# TOP.net
KiCad netlist of a schematic drawn in Altium Designer
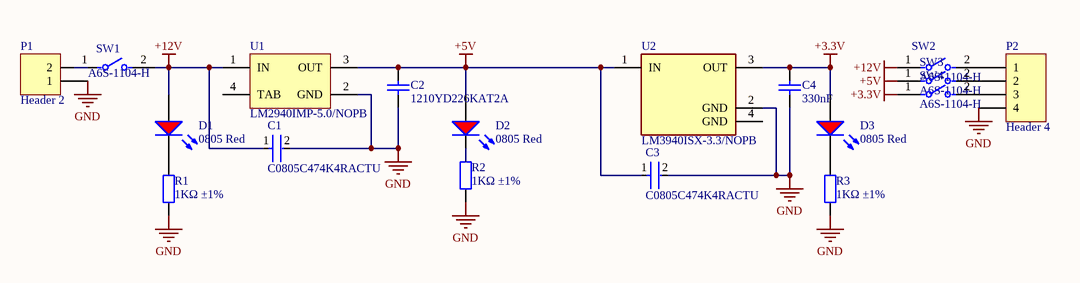
[diagram p0: TOP.SchDoc]

(export (version "E")
  (design (tool "Eeschema 10.0.6"))
  (components
    (comp (ref "C1")
      (value "C0805C474K4RACTU")
      (footprint "FP-C0805C-DN-MFG")
      (description "CAP CER 0.47UF 16V 10% X7R 0805")
      (fields
        (field (name "MANUFACTURER") "KEMET")
        (field (name "OCTOPART") "https://octopart.com/c0805c474k4ractu-kemet-107561")
      )
      (libsource (lib "Altium Content Vault") (part "b4654b650e69147ec39a6b967a45e02"))
    )
    (comp (ref "C2")
      (value "1210YD226KAT2A")
      (footprint "CAPC3225X279X50LL20T25")
      (description "Chip Capacitor, 22 uF, +/- 10%, 16 V, -55 to 85 degC, 1210 (3225 Metric), RoHS, Tape and Reel")
      (fields (field (name "MANUFACTURER") "AVX"))
      (libsource (lib "Altium Content Vault") (part "CAP-NP-2"))
    )
    (comp (ref "C3")
      (value "C0805C474K4RACTU")
      (footprint "FP-C0805C-DN-MFG")
      (description "CAP CER 0.47UF 16V 10% X7R 0805")
      (fields
        (field (name "MANUFACTURER") "KEMET")
        (field (name "OCTOPART") "https://octopart.com/c0805c474k4ractu-kemet-107561")
      )
      (libsource (lib "Altium Content Vault") (part "b4654b650e69147ec39a6b967a45e02"))
    )
    (comp (ref "C4")
      (value "330nF")
      (footprint "0603_C")
      (description "Chip capacitors")
      (fields
        (field (name "MANUFACTURER") "Guangdong Fenghua Advanced Tech")
        (field (name "PARTNUMBER") "0603B334K250NT")
      )
      (libsource (lib "Cap") (part "0603 330nF (334) 10% 25V"))
    )
    (comp (ref "D1")
      (value "0805 Red")
      (footprint "0805_LED_S1")
      (description "LED")
      (fields
        (field (name "PARTNUMBER") "FC-2012HRK-620D")
        (field (name "MANUFACTURER") "Foshan NationStar Optoelectronics")
      )
      (libsource (lib "LED") (part "0805 LED Red"))
    )
    (comp (ref "D2")
      (value "0805 Red")
      (footprint "0805_LED_S1")
      (description "LED")
      (fields
        (field (name "PARTNUMBER") "FC-2012HRK-620D")
        (field (name "MANUFACTURER") "Foshan NationStar Optoelectronics")
      )
      (libsource (lib "LED") (part "0805 LED Red"))
    )
    (comp (ref "D3")
      (value "0805 Red")
      (footprint "0805_LED_S1")
      (description "LED")
      (fields
        (field (name "PARTNUMBER") "FC-2012HRK-620D")
        (field (name "MANUFACTURER") "Foshan NationStar Optoelectronics")
      )
      (libsource (lib "LED") (part "0805 LED Red"))
    )
    (comp (ref "P1")
      (value "Header 2")
      (footprint "HDR1X2")
      (description "Header, 2-Pin")
      (fields (field (name "PUBLISHER") "Altium Limited"))
      (libsource (lib "Miscellaneous Connectors") (part "Header 2"))
    )
    (comp (ref "P2")
      (value "Header 4")
      (footprint "HDR1X4")
      (description "Header, 4-Pin")
      (fields (field (name "PUBLISHER") "Altium Limited"))
      (libsource (lib "Miscellaneous Connectors") (part "Header 4"))
    )
    (comp (ref "R1")
      (value "1KΩ ±1%")
      (footprint "0805_R")
      (description "Chip resistor")
      (fields (field (name "MANUFACTURER") "Uniroyal Elec") (field (name "PARTNUMBER") "0805W8F1001T5E"))
      (libsource (lib "RES") (part "0805 1K (1001) 1%"))
    )
    (comp (ref "R2")
      (value "1KΩ ±1%")
      (footprint "0805_R")
      (description "Chip resistor")
      (fields (field (name "MANUFACTURER") "Uniroyal Elec") (field (name "PARTNUMBER") "0805W8F1001T5E"))
      (libsource (lib "RES") (part "0805 1K (1001) 1%"))
    )
    (comp (ref "R3")
      (value "1KΩ ±1%")
      (footprint "0805_R")
      (description "Chip resistor")
      (fields (field (name "MANUFACTURER") "Uniroyal Elec") (field (name "PARTNUMBER") "0805W8F1001T5E"))
      (libsource (lib "RES") (part "0805 1K (1001) 1%"))
    )
    (comp (ref "SW1")
      (value "A6S-1104-H")
      (footprint "FP-A6S-1104-H-MFG")
      (description "Switch DIP 1 way Raised Slide SMT")
      (fields (field (name "MANUFACTURER") "Omron Electronics Inc-EMC Div"))
      (libsource (lib "Altium Content Vault") (part "bb27bde45df87f1f469753f287ef5ae"))
    )
    (comp (ref "SW2")
      (value "A6S-1104-H")
      (footprint "FP-A6S-1104-H-MFG")
      (description "Switch DIP 1 way Raised Slide SMT")
      (fields (field (name "MANUFACTURER") "Omron Electronics Inc-EMC Div"))
      (libsource (lib "Altium Content Vault") (part "bb27bde45df87f1f469753f287ef5ae"))
    )
    (comp (ref "SW3")
      (value "A6S-1104-H")
      (footprint "FP-A6S-1104-H-MFG")
      (description "Switch DIP 1 way Raised Slide SMT")
      (fields (field (name "MANUFACTURER") "Omron Electronics Inc-EMC Div"))
      (libsource (lib "Altium Content Vault") (part "bb27bde45df87f1f469753f287ef5ae"))
    )
    (comp (ref "SW4")
      (value "A6S-1104-H")
      (footprint "FP-A6S-1104-H-MFG")
      (description "Switch DIP 1 way Raised Slide SMT")
      (fields (field (name "MANUFACTURER") "Omron Electronics Inc-EMC Div"))
      (libsource (lib "Altium Content Vault") (part "bb27bde45df87f1f469753f287ef5ae"))
    )
    (comp (ref "U1")
      (value "LM2940IMP-5.0/NOPB")
      (footprint "DCY0004A_M")
      (description "1A Low Dropout Regulator, 4-pin SOT-223, Pb-Free")
      (fields (field (name "MANUFACTURER") "Texas Instruments"))
      (libsource (lib "Altium Content Vault") (part "PM-REG-LM2940-TO4"))
    )
    (comp (ref "U2")
      (value "LM3940ISX-3.3/NOPB")
      (footprint "FP-KTT0003B-MFG")
      (description "IC REG LIN 3.3V 1A DDPAK/TO263-3")
      (fields
        (field (name "OCTOPART") "https://octopart.com/lm3940isx-3.3%2Fnopb-texas+instruments-24814218")
        (field (name "MANUFACTURER") "Texas Instruments")
      )
      (libsource (lib "Altium Content Vault") (part "5d75afe1045818d72111deb72d0ea28"))
    )
  )
  (nets
    (net (code "1") (name "+3.3V") (class "Default")
      (node (ref "C4") (pin "2") (pinfunction "2_2") (pintype "passive"))
      (node (ref "D3") (pin "A") (pinfunction "A_A") (pintype "passive"))
      (node (ref "SW4") (pin "1") (pinfunction "1_1") (pintype "passive"))
      (node (ref "U2") (pin "3") (pinfunction "OUT_3") (pintype "power_in"))
    )
    (net (code "2") (name "+5V") (class "Default")
      (node (ref "C2") (pin "2") (pinfunction "2_2") (pintype "passive"))
      (node (ref "C3") (pin "1") (pinfunction "1_1") (pintype "passive"))
      (node (ref "D2") (pin "A") (pinfunction "A_A") (pintype "passive"))
      (node (ref "SW3") (pin "1") (pinfunction "1_1") (pintype "passive"))
      (node (ref "U1") (pin "3") (pinfunction "OUT_3") (pintype "power_in"))
      (node (ref "U2") (pin "1") (pinfunction "IN_1") (pintype "power_in"))
    )
    (net (code "3") (name "+12V") (class "Default")
      (node (ref "C1") (pin "1") (pinfunction "1_1") (pintype "passive"))
      (node (ref "D1") (pin "A") (pinfunction "A_A") (pintype "passive"))
      (node (ref "SW1") (pin "2") (pinfunction "2_2") (pintype "passive"))
      (node (ref "SW2") (pin "1") (pinfunction "1_1") (pintype "passive"))
      (node (ref "U1") (pin "1") (pinfunction "IN_1") (pintype "power_in"))
    )
    (net (code "4") (name "GND") (class "Default")
      (node (ref "C1") (pin "2") (pinfunction "2_2") (pintype "passive"))
      (node (ref "C2") (pin "1") (pinfunction "1_1") (pintype "passive"))
      (node (ref "C3") (pin "2") (pinfunction "2_2") (pintype "passive"))
      (node (ref "C4") (pin "1") (pinfunction "1_1") (pintype "passive"))
      (node (ref "P1") (pin "1") (pinfunction "1_1") (pintype "passive"))
      (node (ref "P2") (pin "4") (pinfunction "4_4") (pintype "passive"))
      (node (ref "R1") (pin "1") (pinfunction "1_1") (pintype "passive"))
      (node (ref "R2") (pin "1") (pinfunction "1_1") (pintype "passive"))
      (node (ref "R3") (pin "1") (pinfunction "1_1") (pintype "passive"))
      (node (ref "U1") (pin "2") (pinfunction "GND_2") (pintype "power_in"))
      (node (ref "U2") (pin "2") (pinfunction "GND_2") (pintype "power_in"))
    )
    (net (code "5") (name "Net-(D1-PadK)") (class "Default")
      (node (ref "D1") (pin "K") (pinfunction "K_K") (pintype "passive"))
      (node (ref "R1") (pin "2") (pinfunction "2_2") (pintype "passive"))
    )
    (net (code "6") (name "Net-(D2-PadK)") (class "Default")
      (node (ref "D2") (pin "K") (pinfunction "K_K") (pintype "passive"))
      (node (ref "R2") (pin "2") (pinfunction "2_2") (pintype "passive"))
    )
    (net (code "7") (name "Net-(D3-PadK)") (class "Default")
      (node (ref "D3") (pin "K") (pinfunction "K_K") (pintype "passive"))
      (node (ref "R3") (pin "2") (pinfunction "2_2") (pintype "passive"))
    )
    (net (code "8") (name "Net-(P1-Pad2)") (class "Default")
      (node (ref "P1") (pin "2") (pinfunction "2_2") (pintype "passive"))
      (node (ref "SW1") (pin "1") (pinfunction "1_1") (pintype "passive"))
    )
    (net (code "9") (name "Net-(P2-Pad1)") (class "Default")
      (node (ref "P2") (pin "1") (pinfunction "1_1") (pintype "passive"))
      (node (ref "SW2") (pin "2") (pinfunction "2_2") (pintype "passive"))
    )
    (net (code "10") (name "Net-(P2-Pad2)") (class "Default")
      (node (ref "P2") (pin "2") (pinfunction "2_2") (pintype "passive"))
      (node (ref "SW3") (pin "2") (pinfunction "2_2") (pintype "passive"))
    )
    (net (code "11") (name "Net-(P2-Pad3)") (class "Default")
      (node (ref "P2") (pin "3") (pinfunction "3_3") (pintype "passive"))
      (node (ref "SW4") (pin "2") (pinfunction "2_2") (pintype "passive"))
    )
    (net (code "12") (name "unconnected-(U1-TAB-Pad4)") (class "Default")
      (node (ref "U1") (pin "4") (pinfunction "TAB_4") (pintype "power_in"))
    )
    (net (code "13") (name "unconnected-(U2-GND-Pad4)") (class "Default")
      (node (ref "U2") (pin "4") (pinfunction "GND_4") (pintype "power_in"))
    )
  )
)
